# MOSBRIDGE.net
KiCad netlist of a schematic drawn in EAGLE
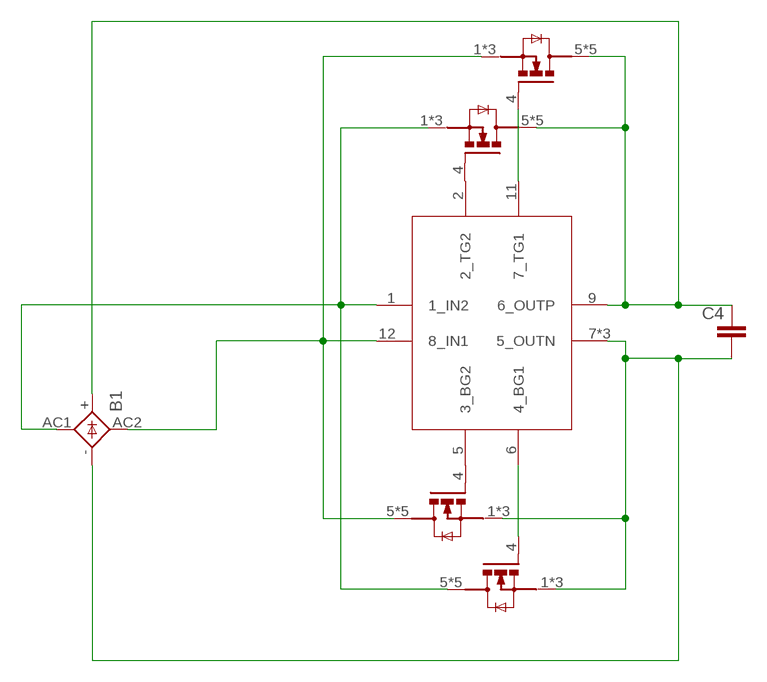
[diagram p0: schematic, sheet 1]

(export (version "E")
  (design (tool "Eeschema 10.0.6"))
  (components
    (comp (ref "B1")
      (value "GBU4")
      (footprint "eagle-import:GBU4S")
      (libsource (lib "eagle-import") (part "GBU4"))
    )
    (comp (ref "C4")
      (value "47uF")
      (footprint "eagle-import:C1206")
      (libsource (lib "eagle-import") (part "C-EUC1206"))
    )
    (comp (ref "Q1")
      (value "MOS_SMDTDSON-8")
      (footprint "eagle-import:PG-TDSON-8")
      (libsource (lib "eagle-import") (part "MOS_SMDTDSON-8"))
    )
    (comp (ref "Q2")
      (value "MOS_SMDTDSON-8")
      (footprint "eagle-import:PG-TDSON-8")
      (libsource (lib "eagle-import") (part "MOS_SMDTDSON-8"))
    )
    (comp (ref "Q3")
      (value "MOS_SMDTDSON-8")
      (footprint "eagle-import:PG-TDSON-8")
      (libsource (lib "eagle-import") (part "MOS_SMDTDSON-8"))
    )
    (comp (ref "Q4")
      (value "MOS_SMDTDSON-8")
      (footprint "eagle-import:PG-TDSON-8")
      (libsource (lib "eagle-import") (part "MOS_SMDTDSON-8"))
    )
    (comp (ref "U$1")
      (value "LT4320MSOP")
      (footprint "eagle-import:LT4320_MSOP")
      (libsource (lib "eagle-import") (part "LT4320MSOP"))
    )
  )
  (nets
    (net (code "1") (name "Net-(B1-AC1)") (class "Default")
      (node (ref "B1") (pin "AC2") (pinfunction "AC1_AC2") (pintype "passive"))
      (node (ref "Q2") (pin "1") (pinfunction "S_1") (pintype "passive"))
      (node (ref "Q2") (pin "2") (pinfunction "S_2") (pintype "passive"))
      (node (ref "Q2") (pin "3") (pinfunction "S_3") (pintype "passive"))
      (node (ref "Q3") (pin "5") (pinfunction "D_5") (pintype "passive"))
      (node (ref "Q3") (pin "6") (pinfunction "D_6") (pintype "passive"))
      (node (ref "Q3") (pin "7") (pinfunction "D_7") (pintype "passive"))
      (node (ref "Q3") (pin "8") (pinfunction "D_8") (pintype "passive"))
      (node (ref "Q3") (pin "TH") (pinfunction "D_TH") (pintype "passive"))
      (node (ref "U$1") (pin "12") (pinfunction "8_IN1_12") (pintype "bidirectional"))
    )
    (net (code "2") (name "Net-(B1-AC2)") (class "Default")
      (node (ref "B1") (pin "AC1") (pinfunction "AC2_AC1") (pintype "passive"))
      (node (ref "Q1") (pin "1") (pinfunction "S_1") (pintype "passive"))
      (node (ref "Q1") (pin "2") (pinfunction "S_2") (pintype "passive"))
      (node (ref "Q1") (pin "3") (pinfunction "S_3") (pintype "passive"))
      (node (ref "Q4") (pin "5") (pinfunction "D_5") (pintype "passive"))
      (node (ref "Q4") (pin "6") (pinfunction "D_6") (pintype "passive"))
      (node (ref "Q4") (pin "7") (pinfunction "D_7") (pintype "passive"))
      (node (ref "Q4") (pin "8") (pinfunction "D_8") (pintype "passive"))
      (node (ref "Q4") (pin "TH") (pinfunction "D_TH") (pintype "passive"))
      (node (ref "U$1") (pin "1") (pinfunction "1_IN2_1") (pintype "bidirectional"))
    )
    (net (code "3") (name "Net-(B1-Pad-)") (class "Default")
      (node (ref "B1") (pin "-") (pinfunction "-_-") (pintype "passive"))
      (node (ref "C4") (pin "2") (pinfunction "2_2") (pintype "passive"))
      (node (ref "Q3") (pin "1") (pinfunction "S_1") (pintype "passive"))
      (node (ref "Q3") (pin "2") (pinfunction "S_2") (pintype "passive"))
      (node (ref "Q3") (pin "3") (pinfunction "S_3") (pintype "passive"))
      (node (ref "Q4") (pin "1") (pinfunction "S_1") (pintype "passive"))
      (node (ref "Q4") (pin "2") (pinfunction "S_2") (pintype "passive"))
      (node (ref "Q4") (pin "3") (pinfunction "S_3") (pintype "passive"))
      (node (ref "U$1") (pin "7") (pinfunction "5_OUTN_7") (pintype "bidirectional"))
      (node (ref "U$1") (pin "EXP") (pinfunction "5_OUTN_EXP") (pintype "bidirectional"))
      (node (ref "U$1") (pin "EXP1") (pinfunction "5_OUTN_EXP1") (pintype "bidirectional"))
    )
    (net (code "4") (name "Net-(Q1-G)") (class "Default")
      (node (ref "Q1") (pin "4") (pinfunction "G_4") (pintype "passive"))
      (node (ref "U$1") (pin "2") (pinfunction "2_TG2_2") (pintype "bidirectional"))
    )
    (net (code "5") (name "Net-(Q2-G)") (class "Default")
      (node (ref "Q2") (pin "4") (pinfunction "G_4") (pintype "passive"))
      (node (ref "U$1") (pin "11") (pinfunction "7_TG1_11") (pintype "bidirectional"))
    )
    (net (code "6") (name "Net-(Q3-G)") (class "Default")
      (node (ref "Q3") (pin "4") (pinfunction "G_4") (pintype "passive"))
      (node (ref "U$1") (pin "5") (pinfunction "3_BG2_5") (pintype "bidirectional"))
    )
    (net (code "7") (name "Net-(Q4-G)") (class "Default")
      (node (ref "Q4") (pin "4") (pinfunction "G_4") (pintype "passive"))
      (node (ref "U$1") (pin "6") (pinfunction "4_BG1_6") (pintype "bidirectional"))
    )
    (net (code "8") (name "Net-(U$1-6_OUTP)") (class "Default")
      (node (ref "B1") (pin "+") (pinfunction "+_+") (pintype "passive"))
      (node (ref "C4") (pin "1") (pinfunction "1_1") (pintype "passive"))
      (node (ref "Q1") (pin "5") (pinfunction "D_5") (pintype "passive"))
      (node (ref "Q1") (pin "6") (pinfunction "D_6") (pintype "passive"))
      (node (ref "Q1") (pin "7") (pinfunction "D_7") (pintype "passive"))
      (node (ref "Q1") (pin "8") (pinfunction "D_8") (pintype "passive"))
      (node (ref "Q1") (pin "TH") (pinfunction "D_TH") (pintype "passive"))
      (node (ref "Q2") (pin "5") (pinfunction "D_5") (pintype "passive"))
      (node (ref "Q2") (pin "6") (pinfunction "D_6") (pintype "passive"))
      (node (ref "Q2") (pin "7") (pinfunction "D_7") (pintype "passive"))
      (node (ref "Q2") (pin "8") (pinfunction "D_8") (pintype "passive"))
      (node (ref "Q2") (pin "TH") (pinfunction "D_TH") (pintype "passive"))
      (node (ref "U$1") (pin "9") (pinfunction "6_OUTP_9") (pintype "bidirectional"))
    )
  )
)
